# MicroController.net
KiCad netlist of a schematic drawn in Altium Designer
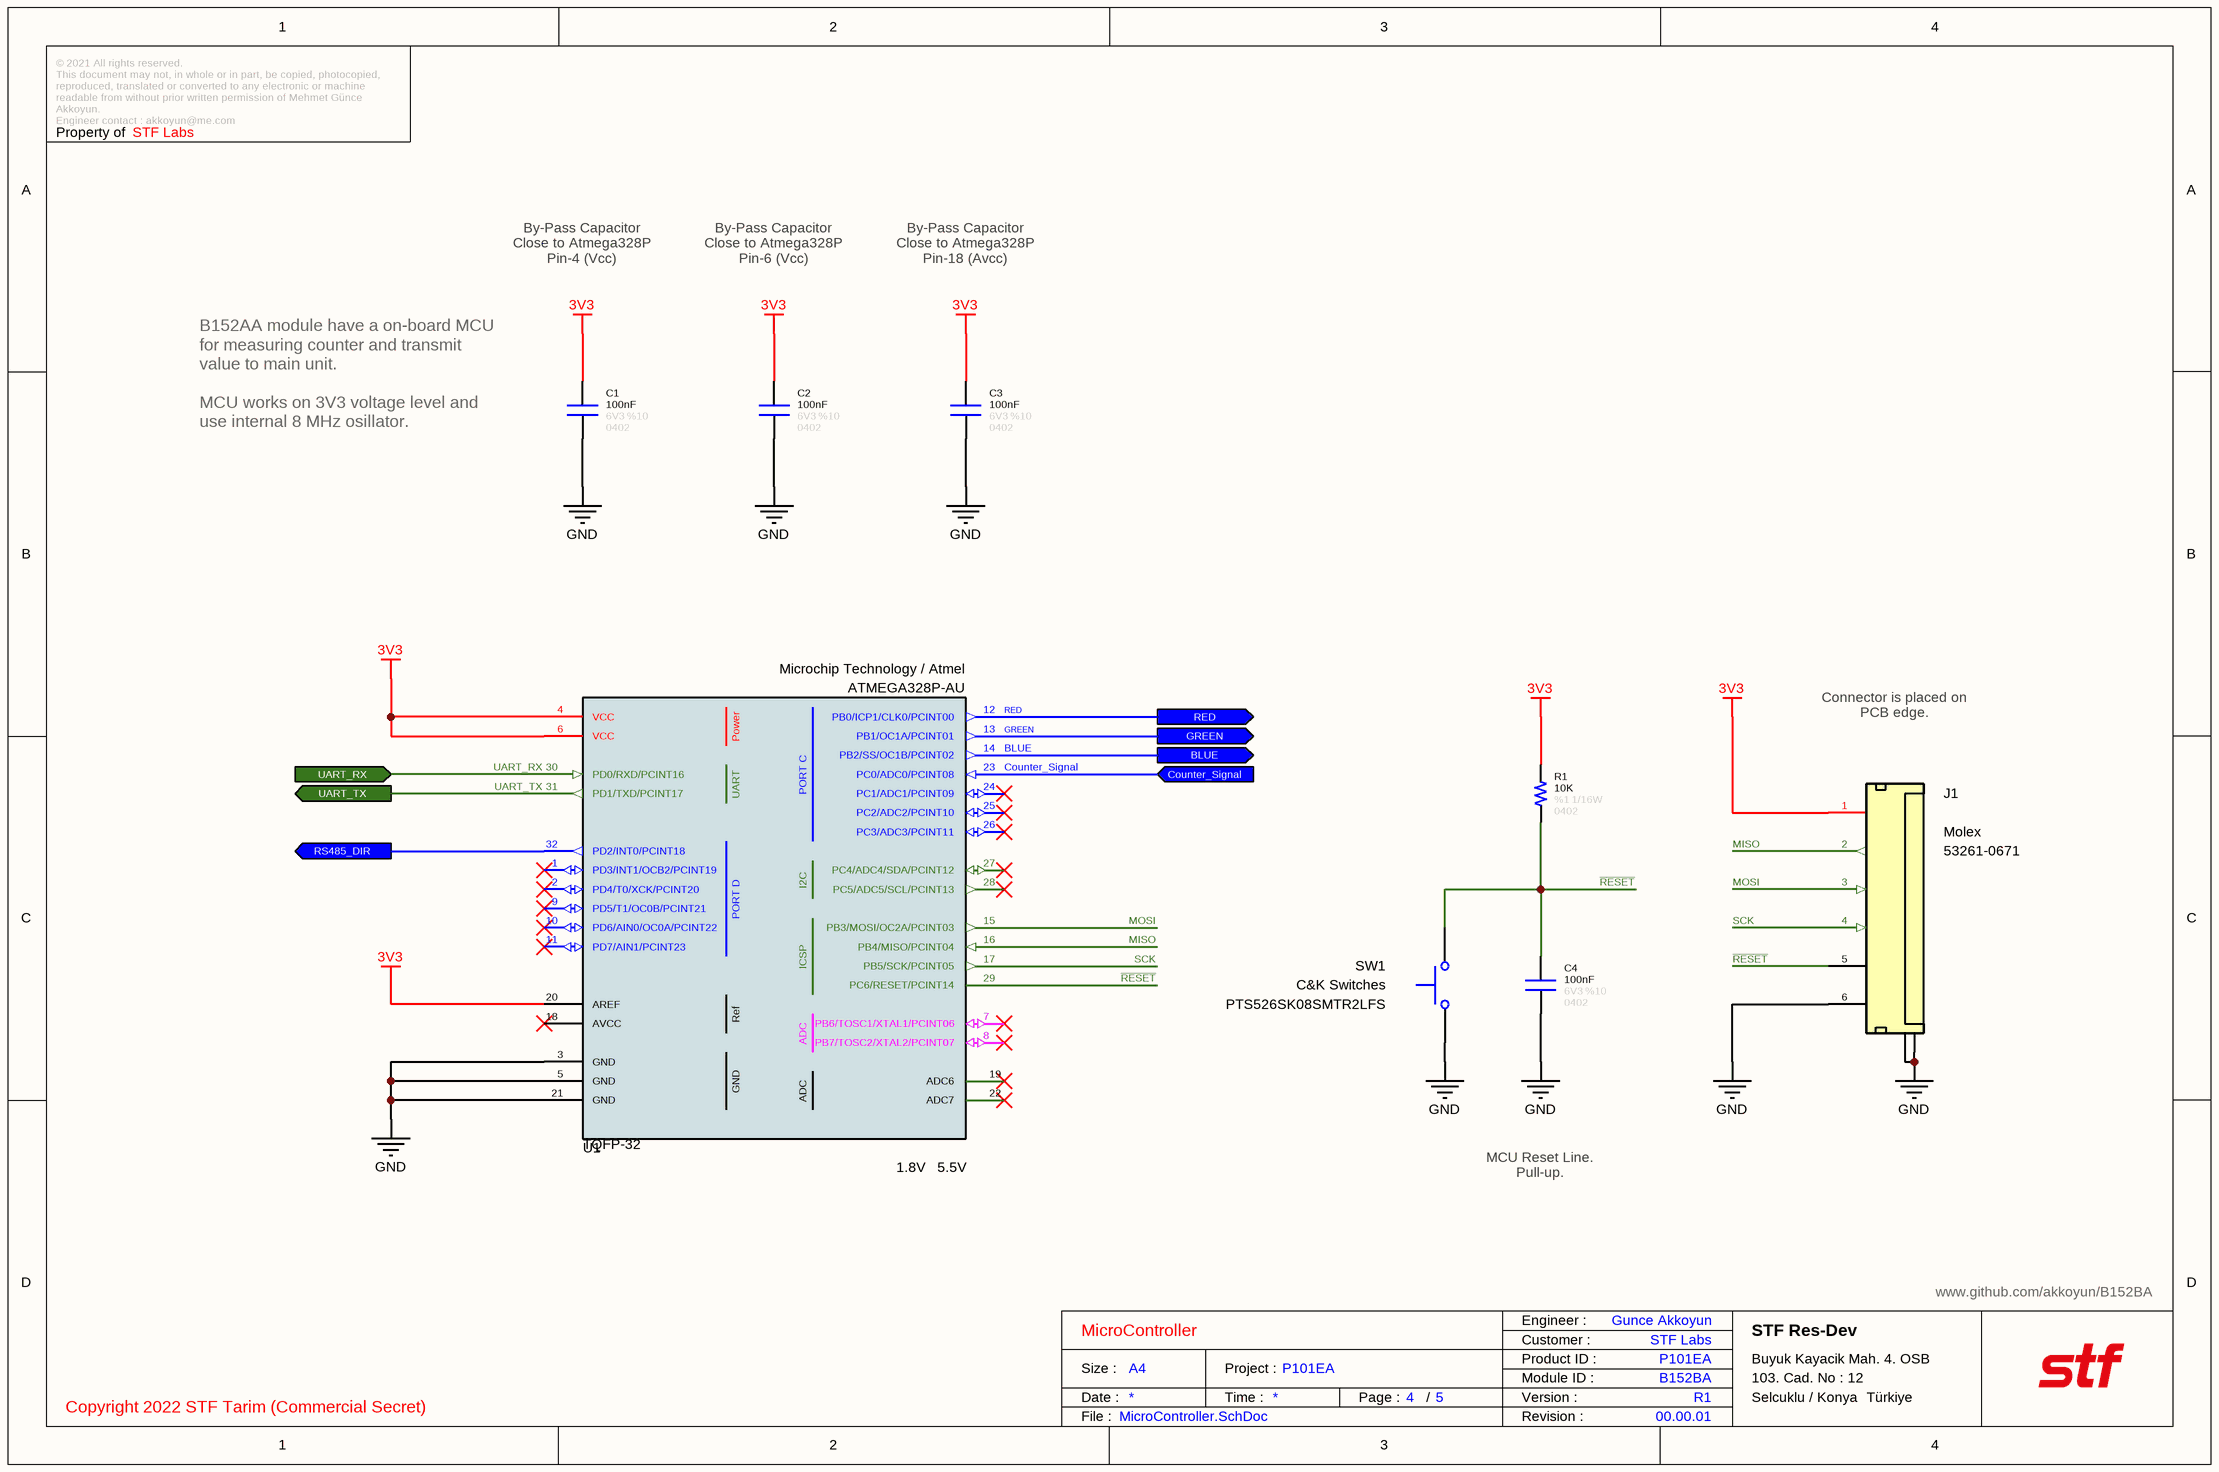
[diagram p0: MicroController.SchDoc]

(export (version "E")
  (design (tool "Eeschema 10.0.6"))
  (components
    (comp (ref "C1")
      (value "100nF")
      (footprint "CAPACITOR_0402")
      (description "Capacitor - 100nF [0402-6V3] (Ceramic)")
      (fields
        (field (name "MANUFACTURER PART NUMBER") "04026D104KAT4A")
        (field (name "TOLERANCE") "%10")
        (field (name "VOLTAGE") "6V3")
        (field (name "CASE") "0402")
      )
      (libsource (lib "Akkoyun") (part "Capacitor - 100nF [0402-6V3]"))
    )
    (comp (ref "C2")
      (value "100nF")
      (footprint "CAPACITOR_0402")
      (description "Capacitor - 100nF [0402-6V3] (Ceramic)")
      (fields
        (field (name "MANUFACTURER PART NUMBER") "04026D104KAT4A")
        (field (name "TOLERANCE") "%10")
        (field (name "VOLTAGE") "6V3")
        (field (name "CASE") "0402")
      )
      (libsource (lib "Akkoyun") (part "Capacitor - 100nF [0402-6V3]"))
    )
    (comp (ref "C3")
      (value "100nF")
      (footprint "CAPACITOR_0402")
      (description "Capacitor - 100nF [0402-6V3] (Ceramic)")
      (fields
        (field (name "MANUFACTURER PART NUMBER") "04026D104KAT4A")
        (field (name "TOLERANCE") "%10")
        (field (name "VOLTAGE") "6V3")
        (field (name "CASE") "0402")
      )
      (libsource (lib "Akkoyun") (part "Capacitor - 100nF [0402-6V3]"))
    )
    (comp (ref "C4")
      (value "100nF")
      (footprint "CAPACITOR_0402")
      (description "Capacitor - 100nF [0402-6V3] (Ceramic)")
      (fields
        (field (name "MANUFACTURER PART NUMBER") "04026D104KAT4A")
        (field (name "TOLERANCE") "%10")
        (field (name "VOLTAGE") "6V3")
        (field (name "CASE") "0402")
      )
      (libsource (lib "Akkoyun") (part "Capacitor - 100nF [0402-6V3]"))
    )
    (comp (ref "J1")
      (value "~")
      (footprint "Connector_Tunic 6P")
      (description "Mini Tunic Connector with 6P")
      (fields
        (field (name "MANUFACTURER PART NUMBER") "53261-0671")
        (field (name "MANUFACTURER NAME") "Molex")
      )
      (libsource (lib "Akkoyun") (part "Connector - Mini Tunic 6P (1.25)"))
    )
    (comp (ref "R1")
      (value "10K")
      (footprint "RESISTOR_0402")
      (description "Thick Film Resistors - SMD 1/16 W 10 KOhm 1%")
      (fields
        (field (name "MANUFACTURER PART NUMBER") "CRCW040210K0FKED")
        (field (name "TOLERANCE") "%1")
        (field (name "CASE") "0402")
        (field (name "POWER") "1/16W")
      )
      (libsource (lib "Akkoyun") (part "Resistor - 10K [0402]"))
    )
    (comp (ref "SW1")
      (value "~")
      (footprint "PTS526_Switch")
      (description "Switch Tactile N.O. SPST Flush Round Button Gull Wing 0.05A 12VDC 200000Cycles 2.45N SMD T/R")
      (fields
        (field (name "MANUFACTURER NAME") "C&K Switches")
        (field (name "MANUFACTURER PART NUMBER") "PTS526SK08SMTR2LFS")
      )
      (libsource (lib "Akkoyun") (part "Switch - Push Button"))
    )
    (comp (ref "U1")
      (value "~")
      (footprint "TQFN-32")
      (description "8-bit Microcontrollers - MCU 32KB In-system Flash 20MHz 1.8V-5.5V")
      (fields
        (field (name "SUPPLY VOLTAGE - MAX") "5.5V")
        (field (name "SUPPLY VOLTAGE - MIN") "1.8V")
        (field (name "MANUFACTURER NAME") "Microchip Technology / Atmel")
        (field (name "MANUFACTURER PART NUMBER") "ATMEGA328P-AU")
        (field (name "CASE") "TQFP-32")
      )
      (libsource (lib "Akkoyun") (part "IC - ATMEGA328P-AU"))
    )
  )
  (nets
    (net (code "1") (name "/BLUE") (class "Default")
      (node (ref "U1") (pin "14") (pinfunction "PB2/SS/OC1B/PCINT02_14") (pintype "output"))
    )
    (net (code "2") (name "/Counter_Signal") (class "Default")
      (node (ref "U1") (pin "23") (pinfunction "PC0/ADC0/PCINT08_23") (pintype "input"))
    )
    (net (code "3") (name "/GREEN") (class "Default")
      (node (ref "U1") (pin "13") (pinfunction "PB1/OC1A/PCINT01_13") (pintype "output"))
    )
    (net (code "4") (name "/MISO") (class "Default")
      (node (ref "J1") (pin "2") (pinfunction "MISO_2") (pintype "output"))
      (node (ref "U1") (pin "16") (pinfunction "PB4/MISO/PCINT04_16") (pintype "input"))
    )
    (net (code "5") (name "/MOSI") (class "Default")
      (node (ref "J1") (pin "3") (pinfunction "MOSI_3") (pintype "input"))
      (node (ref "U1") (pin "15") (pinfunction "PB3/MOSI/OC2A/PCINT03_15") (pintype "output"))
    )
    (net (code "6") (name "/RED") (class "Default")
      (node (ref "U1") (pin "12") (pinfunction "PB0/ICP1/CLK0/PCINT00_12") (pintype "output"))
    )
    (net (code "7") (name "/RS485_DIR") (class "Default")
      (node (ref "U1") (pin "32") (pinfunction "PD2/INT0/PCINT18_32") (pintype "output"))
    )
    (net (code "8") (name "/SCK") (class "Default")
      (node (ref "J1") (pin "4") (pinfunction "SCK_4") (pintype "input"))
      (node (ref "U1") (pin "17") (pinfunction "PB5/SCK/PCINT05_17") (pintype "output"))
    )
    (net (code "9") (name "/UART_RX") (class "Default")
      (node (ref "U1") (pin "30") (pinfunction "PD0/RXD/PCINT16_30") (pintype "input"))
    )
    (net (code "10") (name "/UART_TX") (class "Default")
      (node (ref "U1") (pin "31") (pinfunction "PD1/TXD/PCINT17_31") (pintype "output"))
    )
    (net (code "11") (name "/~{RESET}") (class "Default")
      (node (ref "C4") (pin "2") (pinfunction "2_2") (pintype "passive"))
      (node (ref "J1") (pin "5") (pinfunction "RESET_5") (pintype "passive"))
      (node (ref "R1") (pin "1") (pinfunction "1_1") (pintype "passive"))
      (node (ref "SW1") (pin "2") (pinfunction "COM_2") (pintype "passive"))
      (node (ref "U1") (pin "29") (pinfunction "PC6/RESET/PCINT14_29") (pintype "passive"))
    )
    (net (code "12") (name "3V3") (class "Default")
      (node (ref "C1") (pin "2") (pinfunction "2_2") (pintype "passive"))
      (node (ref "C2") (pin "2") (pinfunction "2_2") (pintype "passive"))
      (node (ref "C3") (pin "2") (pinfunction "2_2") (pintype "passive"))
      (node (ref "J1") (pin "1") (pinfunction "VCC_1") (pintype "power_in"))
      (node (ref "R1") (pin "2") (pinfunction "2_2") (pintype "passive"))
      (node (ref "U1") (pin "20") (pinfunction "AREF_20") (pintype "passive"))
      (node (ref "U1") (pin "4") (pinfunction "VCC_4") (pintype "power_in"))
      (node (ref "U1") (pin "6") (pinfunction "VCC_6") (pintype "power_in"))
    )
    (net (code "13") (name "GND") (class "Default")
      (node (ref "C1") (pin "1") (pinfunction "1_1") (pintype "passive"))
      (node (ref "C2") (pin "1") (pinfunction "1_1") (pintype "passive"))
      (node (ref "C3") (pin "1") (pinfunction "1_1") (pintype "passive"))
      (node (ref "C4") (pin "1") (pinfunction "1_1") (pintype "passive"))
      (node (ref "J1") (pin "6") (pinfunction "GND_6") (pintype "power_in"))
      (node (ref "J1") (pin "7") (pinfunction "GND_7") (pintype "passive"))
      (node (ref "J1") (pin "8") (pinfunction "GND_8") (pintype "passive"))
      (node (ref "SW1") (pin "1") (pinfunction "NC_1") (pintype "passive"))
      (node (ref "U1") (pin "21") (pinfunction "GND_21") (pintype "power_in"))
      (node (ref "U1") (pin "3") (pinfunction "GND_3") (pintype "power_in"))
      (node (ref "U1") (pin "5") (pinfunction "GND_5") (pintype "power_in"))
    )
    (net (code "14") (name "unconnected-(U1-ADC6-Pad19)") (class "Default")
      (node (ref "U1") (pin "19") (pinfunction "ADC6_19") (pintype "passive+no_connect"))
    )
    (net (code "15") (name "unconnected-(U1-ADC7-Pad22)") (class "Default")
      (node (ref "U1") (pin "22") (pinfunction "ADC7_22") (pintype "passive+no_connect"))
    )
    (net (code "16") (name "unconnected-(U1-AVCC-Pad18)") (class "Default")
      (node (ref "U1") (pin "18") (pinfunction "AVCC_18") (pintype "passive+no_connect"))
    )
    (net (code "17") (name "unconnected-(U1-PB6{slash}TOSC1{slash}XTAL1{slash}PCINT06-Pad7)") (class "Default")
      (node (ref "U1") (pin "7") (pinfunction "PB6/TOSC1/XTAL1/PCINT06_7") (pintype "bidirectional+no_connect"))
    )
    (net (code "18") (name "unconnected-(U1-PB7{slash}TOSC2{slash}XTAL2{slash}PCINT07-Pad8)") (class "Default")
      (node (ref "U1") (pin "8") (pinfunction "PB7/TOSC2/XTAL2/PCINT07_8") (pintype "bidirectional+no_connect"))
    )
    (net (code "19") (name "unconnected-(U1-PC1{slash}ADC1{slash}PCINT09-Pad24)") (class "Default")
      (node (ref "U1") (pin "24") (pinfunction "PC1/ADC1/PCINT09_24") (pintype "bidirectional+no_connect"))
    )
    (net (code "20") (name "unconnected-(U1-PC2{slash}ADC2{slash}PCINT10-Pad25)") (class "Default")
      (node (ref "U1") (pin "25") (pinfunction "PC2/ADC2/PCINT10_25") (pintype "bidirectional+no_connect"))
    )
    (net (code "21") (name "unconnected-(U1-PC3{slash}ADC3{slash}PCINT11-Pad26)") (class "Default")
      (node (ref "U1") (pin "26") (pinfunction "PC3/ADC3/PCINT11_26") (pintype "bidirectional+no_connect"))
    )
    (net (code "22") (name "unconnected-(U1-PC4{slash}ADC4{slash}SDA{slash}PCINT12-Pad27)") (class "Default")
      (node (ref "U1") (pin "27") (pinfunction "PC4/ADC4/SDA/PCINT12_27") (pintype "bidirectional+no_connect"))
    )
    (net (code "23") (name "unconnected-(U1-PC5{slash}ADC5{slash}SCL{slash}PCINT13-Pad28)") (class "Default")
      (node (ref "U1") (pin "28") (pinfunction "PC5/ADC5/SCL/PCINT13_28") (pintype "output+no_connect"))
    )
    (net (code "24") (name "unconnected-(U1-PD3{slash}INT1{slash}OCB2{slash}PCINT19-Pad1)") (class "Default")
      (node (ref "U1") (pin "1") (pinfunction "PD3/INT1/OCB2/PCINT19_1") (pintype "bidirectional+no_connect"))
    )
    (net (code "25") (name "unconnected-(U1-PD4{slash}T0{slash}XCK{slash}PCINT20-Pad2)") (class "Default")
      (node (ref "U1") (pin "2") (pinfunction "PD4/T0/XCK/PCINT20_2") (pintype "bidirectional+no_connect"))
    )
    (net (code "26") (name "unconnected-(U1-PD5{slash}T1{slash}OC0B{slash}PCINT21-Pad9)") (class "Default")
      (node (ref "U1") (pin "9") (pinfunction "PD5/T1/OC0B/PCINT21_9") (pintype "bidirectional+no_connect"))
    )
    (net (code "27") (name "unconnected-(U1-PD6{slash}AIN0{slash}OC0A{slash}PCINT22-Pad10)") (class "Default")
      (node (ref "U1") (pin "10") (pinfunction "PD6/AIN0/OC0A/PCINT22_10") (pintype "bidirectional+no_connect"))
    )
    (net (code "28") (name "unconnected-(U1-PD7{slash}AIN1{slash}PCINT23-Pad11)") (class "Default")
      (node (ref "U1") (pin "11") (pinfunction "PD7/AIN1/PCINT23_11") (pintype "bidirectional+no_connect"))
    )
  )
)
